# CH32M030C8T7-R0.net
KiCad netlist of a schematic drawn in Altium Designer
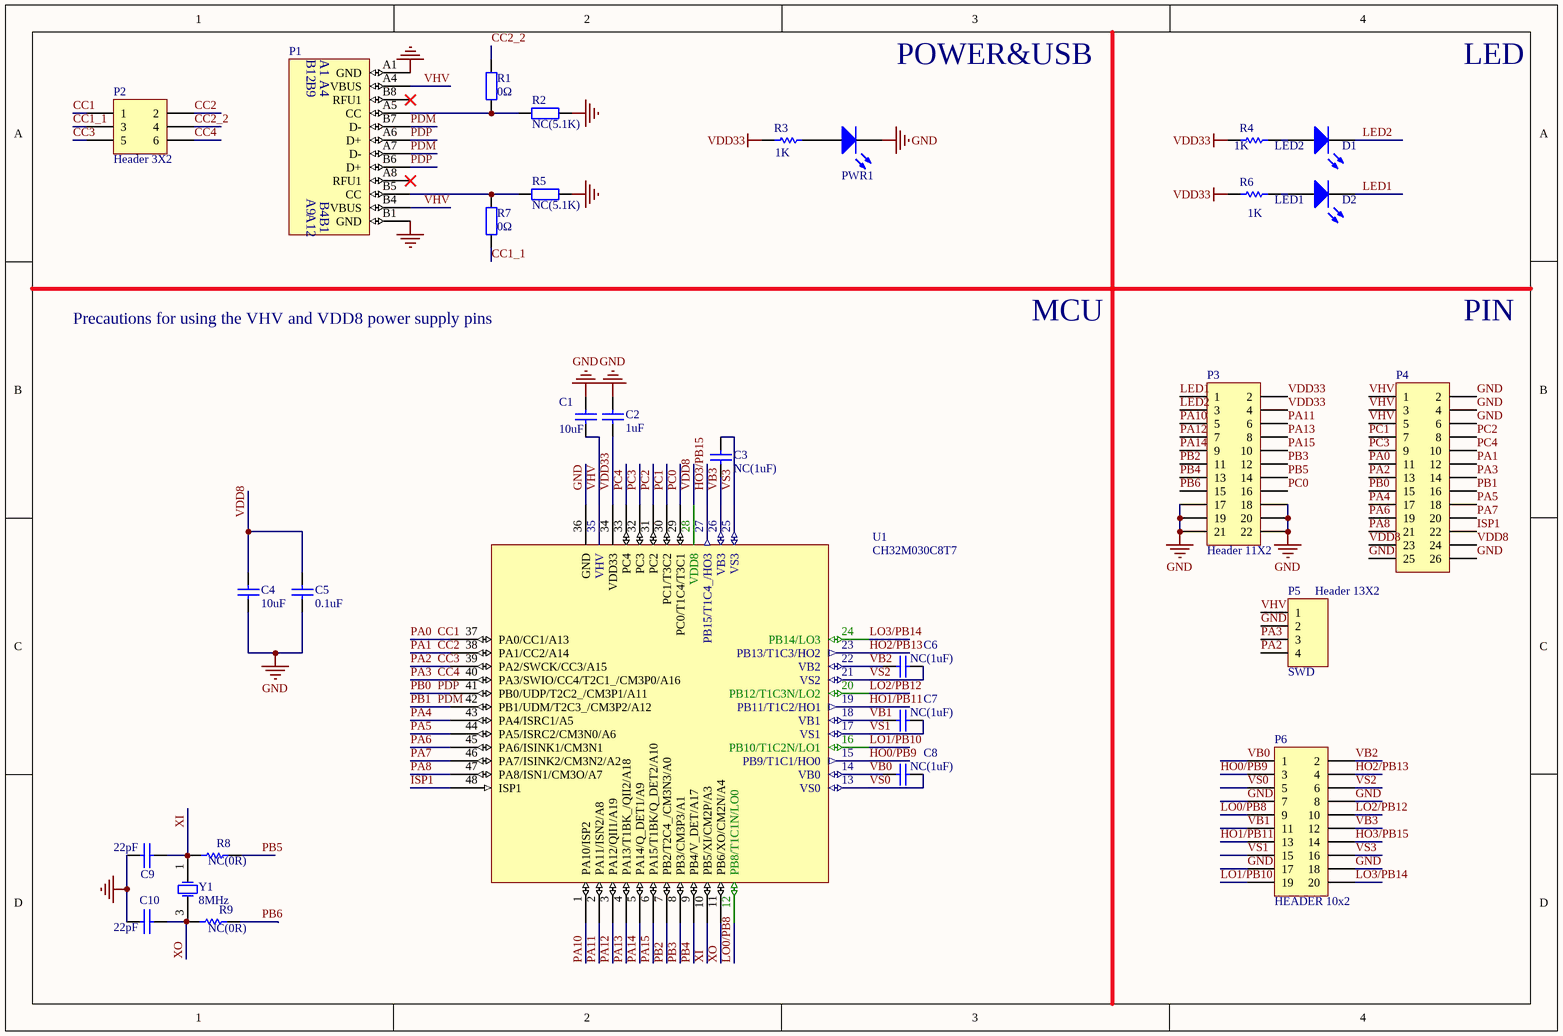
[diagram p0: CH32M030C8T7-R0.SchDoc]

(export (version "E")
  (design (tool "Eeschema 10.0.6"))
  (components
    (comp (ref "C1")
      (value "10uF")
      (footprint "0603_C")
      (description "Capacitor")
      (fields (field (name "PUBLISHER") "Altium Limited"))
      (libsource (lib "*") (part "Cap"))
    )
    (comp (ref "C2")
      (value "1uF")
      (footprint "0603_C")
      (description "Capacitor")
      (fields (field (name "PUBLISHER") "Altium Limited"))
      (libsource (lib "*") (part "Cap"))
    )
    (comp (ref "C3")
      (value "NC(1uF)")
      (footprint "0603_C")
      (description "Capacitor")
      (fields (field (name "PUBLISHER") "Altium Limited"))
      (libsource (lib "*") (part "Cap"))
    )
    (comp (ref "C4")
      (value "10uF")
      (footprint "0603_C")
      (description "Capacitor")
      (fields (field (name "PUBLISHER") "Altium Limited"))
      (libsource (lib "*") (part "Cap"))
    )
    (comp (ref "C5")
      (value "0.1uF")
      (footprint "0603_C")
      (description "Capacitor")
      (fields (field (name "PUBLISHER") "Altium Limited"))
      (libsource (lib "*") (part "Cap"))
    )
    (comp (ref "C6")
      (value "NC(1uF)")
      (footprint "0603_C")
      (description "Capacitor")
      (fields (field (name "PUBLISHER") "Altium Limited"))
      (libsource (lib "*") (part "Cap"))
    )
    (comp (ref "C7")
      (value "NC(1uF)")
      (footprint "0603_C")
      (description "Capacitor")
      (fields (field (name "PUBLISHER") "Altium Limited"))
      (libsource (lib "*") (part "Cap"))
    )
    (comp (ref "C8")
      (value "NC(1uF)")
      (footprint "0603_C")
      (description "Capacitor")
      (fields (field (name "PUBLISHER") "Altium Limited"))
      (libsource (lib "*") (part "Cap"))
    )
    (comp (ref "C9")
      (value "22pF")
      (footprint "0603_C")
      (description "Capacitor")
      (libsource (lib "*") (part "CAP"))
    )
    (comp (ref "C10")
      (value "22pF")
      (footprint "0603_C")
      (description "Capacitor")
      (libsource (lib "*") (part "CAP"))
    )
    (comp (ref "D1")
      (value "LED2")
      (footprint "0603+")
      (description "Typical INFRARED GaAs LED")
      (fields (field (name "PUBLISHER") "Altium Limited"))
      (libsource (lib "*") (part "LED0"))
    )
    (comp (ref "D2")
      (value "LED1")
      (footprint "0603+")
      (description "Typical INFRARED GaAs LED")
      (fields (field (name "PUBLISHER") "Altium Limited"))
      (libsource (lib "*") (part "LED0"))
    )
    (comp (ref "P1")
      (value "TYPE-C")
      (footprint "TYPE-C-Receptacle-2.0")
      (libsource (lib "*") (part "TYPE-C1"))
    )
    (comp (ref "P2")
      (value "Header 3X2")
      (footprint "IDC6-2.54mm")
      (description "Header, 3-Pin, Dual row")
      (fields (field (name "PUBLISHER") "Altium Limited"))
      (libsource (lib "Miscellaneous Connectors") (part "Header 3X2"))
    )
    (comp (ref "P3")
      (value "Header 11X2")
      (footprint "IDC22-2.54mm")
      (description "Header, 11-Pin, Dual row")
      (fields (field (name "PUBLISHER") "Altium Limited"))
      (libsource (lib "Miscellaneous Connectors") (part "Header 11X2"))
    )
    (comp (ref "P4")
      (value "Header 13X2")
      (footprint "IDC26-2.54mm")
      (description "Header, 13-Pin, Dual row")
      (fields (field (name "PUBLISHER") "Altium Limited"))
      (libsource (lib "Miscellaneous Connectors") (part "Header 13X2"))
    )
    (comp (ref "P5")
      (value "SWD")
      (footprint "SIP4-2.54mm")
      (description "Header, 4-Pin")
      (libsource (lib "wch_sch_others") (part "HEADER 4"))
    )
    (comp (ref "P6")
      (value "HEADER 10x2")
      (footprint "MYPCB:IDC20-2.54MM")
      (description "Header, 10-Pin, Dual row")
      (libsource (lib "wch_sch_others") (part "HEADER 10x2"))
    )
    (comp (ref "PWR1")
      (value "POWER  red")
      (footprint "0603+")
      (description "Typical INFRARED GaAs LED")
      (fields (field (name "PUBLISHER") "Altium Limited"))
      (libsource (lib "*") (part "LED0"))
    )
    (comp (ref "R1")
      (value "0Ω")
      (footprint "0603")
      (description "Resistor")
      (libsource (lib "") (part "Res2_1"))
    )
    (comp (ref "R2")
      (value "NC(5.1K)")
      (footprint "0603")
      (description "Resistor")
      (libsource (lib "Miscellaneous Devices") (part "Res2"))
    )
    (comp (ref "R3")
      (value "1K")
      (footprint "0603")
      (description "Semiconductor Resistor")
      (fields (field (name "PUBLISHER") "Altium Limited"))
      (libsource (lib "*") (part "Res Semi"))
    )
    (comp (ref "R4")
      (value "1K")
      (footprint "0603")
      (description "Semiconductor Resistor")
      (fields (field (name "PUBLISHER") "Altium Limited"))
      (libsource (lib "*") (part "Res Semi"))
    )
    (comp (ref "R5")
      (value "NC(5.1K)")
      (footprint "0603")
      (description "Resistor")
      (libsource (lib "Miscellaneous Devices") (part "Res2"))
    )
    (comp (ref "R6")
      (value "1K")
      (footprint "0603")
      (description "Semiconductor Resistor")
      (fields (field (name "PUBLISHER") "Altium Limited"))
      (libsource (lib "*") (part "Res Semi"))
    )
    (comp (ref "R7")
      (value "0Ω")
      (footprint "0603")
      (description "Resistor")
      (libsource (lib "") (part "Res2_1"))
    )
    (comp (ref "R8")
      (value "NC(0R)")
      (footprint "0603")
      (description "Semiconductor Resistor")
      (fields (field (name "PUBLISHER") "Altium Limited"))
      (libsource (lib "*") (part "Res Semi"))
    )
    (comp (ref "R9")
      (value "NC(0R)")
      (footprint "0603")
      (description "Semiconductor Resistor")
      (fields (field (name "PUBLISHER") "Altium Limited"))
      (libsource (lib "*") (part "Res Semi"))
    )
    (comp (ref "U1")
      (value "CH32M030C8T7")
      (footprint "LQFP48")
      (description "RISC-V MCU, 72MHz, USB, Type-C/PD, OPA, CMP, 28V gate driver")
      (libsource (lib "CHXXX") (part "CH32M030C8T7"))
    )
    (comp (ref "Y1")
      (value "8MHz")
      (footprint "XT3225")
      (description "Crystal Oscillator")
      (fields (field (name "PUBLISHER") "Altium Limited"))
      (libsource (lib "*") (part "XTAL"))
    )
  )
  (nets
    (net (code "1") (name "/CC1") (class "Default")
      (node (ref "P2") (pin "1") (pinfunction "1_1") (pintype "passive"))
      (node (ref "P4") (pin "11") (pinfunction "11_11") (pintype "passive"))
      (node (ref "U1") (pin "37") (pinfunction "PA0/CC1/A13_37") (pintype "bidirectional"))
    )
    (net (code "2") (name "/CC1_1") (class "Default")
      (node (ref "P2") (pin "3") (pinfunction "3_3") (pintype "passive"))
      (node (ref "R7") (pin "1") (pinfunction "1_1") (pintype "passive"))
    )
    (net (code "3") (name "/CC2") (class "Default")
      (node (ref "P2") (pin "2") (pinfunction "2_2") (pintype "passive"))
      (node (ref "P4") (pin "12") (pinfunction "12_12") (pintype "passive"))
      (node (ref "U1") (pin "38") (pinfunction "PA1/CC2/A14_38") (pintype "bidirectional"))
    )
    (net (code "4") (name "/CC2_2") (class "Default")
      (node (ref "P2") (pin "4") (pinfunction "4_4") (pintype "passive"))
      (node (ref "R1") (pin "2") (pinfunction "2_2") (pintype "passive"))
    )
    (net (code "5") (name "/CC3") (class "Default")
      (node (ref "P2") (pin "5") (pinfunction "5_5") (pintype "passive"))
      (node (ref "P4") (pin "13") (pinfunction "13_13") (pintype "passive"))
      (node (ref "P5") (pin "4") (pinfunction "4_4") (pintype "passive"))
      (node (ref "U1") (pin "39") (pinfunction "PA2/SWCK/CC3/A15_39") (pintype "bidirectional"))
    )
    (net (code "6") (name "/CC4") (class "Default")
      (node (ref "P2") (pin "6") (pinfunction "6_6") (pintype "passive"))
      (node (ref "P4") (pin "14") (pinfunction "14_14") (pintype "passive"))
      (node (ref "P5") (pin "3") (pinfunction "3_3") (pintype "passive"))
      (node (ref "U1") (pin "40") (pinfunction "PA3/SWIO/CC4/T2C1_/CM3P0/A16_40") (pintype "bidirectional"))
    )
    (net (code "7") (name "/HO0{slash}PB9") (class "Default")
      (node (ref "P6") (pin "3") (pinfunction "3_3") (pintype "passive"))
      (node (ref "U1") (pin "15") (pinfunction "PB9/T1C1/HO0_15") (pintype "output"))
    )
    (net (code "8") (name "/HO1{slash}PB11") (class "Default")
      (node (ref "P6") (pin "13") (pinfunction "13_13") (pintype "passive"))
      (node (ref "U1") (pin "19") (pinfunction "PB11/T1C2/HO1_19") (pintype "output"))
    )
    (net (code "9") (name "/HO2{slash}PB13") (class "Default")
      (node (ref "P6") (pin "4") (pinfunction "4_4") (pintype "passive"))
      (node (ref "U1") (pin "23") (pinfunction "PB13/T1C3/HO2_23") (pintype "output"))
    )
    (net (code "10") (name "/HO3{slash}PB15") (class "Default")
      (node (ref "P6") (pin "14") (pinfunction "14_14") (pintype "passive"))
      (node (ref "U1") (pin "27") (pinfunction "PB15/T1C4_/HO3_27") (pintype "output"))
    )
    (net (code "11") (name "/ISP1") (class "Default")
      (node (ref "P4") (pin "22") (pinfunction "22_22") (pintype "passive"))
      (node (ref "U1") (pin "48") (pinfunction "ISP1_48") (pintype "input"))
    )
    (net (code "12") (name "/LED1") (class "Default")
      (node (ref "D2") (pin "2") (pinfunction "K_2") (pintype "passive"))
      (node (ref "P3") (pin "1") (pinfunction "1_1") (pintype "passive"))
    )
    (net (code "13") (name "/LED2") (class "Default")
      (node (ref "D1") (pin "2") (pinfunction "K_2") (pintype "passive"))
      (node (ref "P3") (pin "3") (pinfunction "3_3") (pintype "passive"))
    )
    (net (code "14") (name "/LO0{slash}PB8") (class "Default")
      (node (ref "P6") (pin "9") (pinfunction "9_9") (pintype "passive"))
      (node (ref "U1") (pin "12") (pinfunction "PB8/T1C1N/LO0_12") (pintype "bidirectional"))
    )
    (net (code "15") (name "/LO1{slash}PB10") (class "Default")
      (node (ref "P6") (pin "19") (pinfunction "19_19") (pintype "passive"))
      (node (ref "U1") (pin "16") (pinfunction "PB10/T1C2N/LO1_16") (pintype "bidirectional"))
    )
    (net (code "16") (name "/LO2{slash}PB12") (class "Default")
      (node (ref "P6") (pin "10") (pinfunction "10_10") (pintype "passive"))
      (node (ref "U1") (pin "20") (pinfunction "PB12/T1C3N/LO2_20") (pintype "bidirectional"))
    )
    (net (code "17") (name "/LO3{slash}PB14") (class "Default")
      (node (ref "P6") (pin "20") (pinfunction "20_20") (pintype "passive"))
      (node (ref "U1") (pin "24") (pinfunction "PB14/LO3_24") (pintype "bidirectional"))
    )
    (net (code "18") (name "/PA4") (class "Default")
      (node (ref "P4") (pin "17") (pinfunction "17_17") (pintype "passive"))
      (node (ref "U1") (pin "43") (pinfunction "PA4/ISRC1/A5_43") (pintype "bidirectional"))
    )
    (net (code "19") (name "/PA5") (class "Default")
      (node (ref "P4") (pin "18") (pinfunction "18_18") (pintype "passive"))
      (node (ref "U1") (pin "44") (pinfunction "PA5/ISRC2/CM3N0/A6_44") (pintype "bidirectional"))
    )
    (net (code "20") (name "/PA6") (class "Default")
      (node (ref "P4") (pin "19") (pinfunction "19_19") (pintype "passive"))
      (node (ref "U1") (pin "45") (pinfunction "PA6/ISINK1/CM3N1_45") (pintype "bidirectional"))
    )
    (net (code "21") (name "/PA7") (class "Default")
      (node (ref "P4") (pin "20") (pinfunction "20_20") (pintype "passive"))
      (node (ref "U1") (pin "46") (pinfunction "PA7/ISINK2/CM3N2/A2_46") (pintype "bidirectional"))
    )
    (net (code "22") (name "/PA8") (class "Default")
      (node (ref "P4") (pin "21") (pinfunction "21_21") (pintype "passive"))
      (node (ref "U1") (pin "47") (pinfunction "PA8/ISN1/CM3O/A7_47") (pintype "bidirectional"))
    )
    (net (code "23") (name "/PA10") (class "Default")
      (node (ref "P3") (pin "5") (pinfunction "5_5") (pintype "passive"))
      (node (ref "U1") (pin "1") (pinfunction "PA10/ISP2_1") (pintype "bidirectional"))
    )
    (net (code "24") (name "/PA11") (class "Default")
      (node (ref "P3") (pin "6") (pinfunction "6_6") (pintype "passive"))
      (node (ref "U1") (pin "2") (pinfunction "PA11/ISN2/A8_2") (pintype "bidirectional"))
    )
    (net (code "25") (name "/PA12") (class "Default")
      (node (ref "P3") (pin "7") (pinfunction "7_7") (pintype "passive"))
      (node (ref "U1") (pin "3") (pinfunction "PA12/QII1/A19_3") (pintype "bidirectional"))
    )
    (net (code "26") (name "/PA13") (class "Default")
      (node (ref "P3") (pin "8") (pinfunction "8_8") (pintype "passive"))
      (node (ref "U1") (pin "4") (pinfunction "PA13/T1BK_/QII2/A18_4") (pintype "bidirectional"))
    )
    (net (code "27") (name "/PA14") (class "Default")
      (node (ref "P3") (pin "9") (pinfunction "9_9") (pintype "passive"))
      (node (ref "U1") (pin "5") (pinfunction "PA14/Q_DET1/A9_5") (pintype "bidirectional"))
    )
    (net (code "28") (name "/PA15") (class "Default")
      (node (ref "P3") (pin "10") (pinfunction "10_10") (pintype "passive"))
      (node (ref "U1") (pin "6") (pinfunction "PA15/T1BK/Q_DET2/A10_6") (pintype "bidirectional"))
    )
    (net (code "29") (name "/PB0") (class "Default")
      (node (ref "P1") (pin "A6") (pinfunction "D+_A6") (pintype "bidirectional"))
      (node (ref "P1") (pin "B6") (pinfunction "D+_B6") (pintype "bidirectional"))
      (node (ref "P4") (pin "15") (pinfunction "15_15") (pintype "passive"))
      (node (ref "U1") (pin "41") (pinfunction "PB0/UDP/T2C2_/CM3P1/A11_41") (pintype "bidirectional"))
    )
    (net (code "30") (name "/PB1") (class "Default")
      (node (ref "P1") (pin "A7") (pinfunction "D-_A7") (pintype "bidirectional"))
      (node (ref "P1") (pin "B7") (pinfunction "D-_B7") (pintype "bidirectional"))
      (node (ref "P4") (pin "16") (pinfunction "16_16") (pintype "passive"))
      (node (ref "U1") (pin "42") (pinfunction "PB1/UDM/T2C3_/CM3P2/A12_42") (pintype "bidirectional"))
    )
    (net (code "31") (name "/PB2") (class "Default")
      (node (ref "P3") (pin "11") (pinfunction "11_11") (pintype "passive"))
      (node (ref "U1") (pin "7") (pinfunction "PB2/T2C4_/CM3N3/A0_7") (pintype "bidirectional"))
    )
    (net (code "32") (name "/PB3") (class "Default")
      (node (ref "P3") (pin "12") (pinfunction "12_12") (pintype "passive"))
      (node (ref "U1") (pin "8") (pinfunction "PB3/CM3P3/A1_8") (pintype "bidirectional"))
    )
    (net (code "33") (name "/PB4") (class "Default")
      (node (ref "P3") (pin "13") (pinfunction "13_13") (pintype "passive"))
      (node (ref "U1") (pin "9") (pinfunction "PB4/V_DET/A17_9") (pintype "bidirectional"))
    )
    (net (code "34") (name "/PB5") (class "Default")
      (node (ref "P3") (pin "14") (pinfunction "14_14") (pintype "passive"))
      (node (ref "R8") (pin "2") (pinfunction "2_2") (pintype "passive"))
    )
    (net (code "35") (name "/PB6") (class "Default")
      (node (ref "P3") (pin "15") (pinfunction "15_15") (pintype "passive"))
      (node (ref "R9") (pin "2") (pinfunction "2_2") (pintype "passive"))
    )
    (net (code "36") (name "/PC0") (class "Default")
      (node (ref "P3") (pin "16") (pinfunction "16_16") (pintype "passive"))
      (node (ref "U1") (pin "29") (pinfunction "PC0/T1C4/T3C1_29") (pintype "bidirectional"))
    )
    (net (code "37") (name "/PC1") (class "Default")
      (node (ref "P4") (pin "7") (pinfunction "7_7") (pintype "passive"))
      (node (ref "U1") (pin "30") (pinfunction "PC1/T3C2_30") (pintype "bidirectional"))
    )
    (net (code "38") (name "/PC2") (class "Default")
      (node (ref "P4") (pin "8") (pinfunction "8_8") (pintype "passive"))
      (node (ref "U1") (pin "31") (pinfunction "PC2_31") (pintype "bidirectional"))
    )
    (net (code "39") (name "/PC3") (class "Default")
      (node (ref "P4") (pin "9") (pinfunction "9_9") (pintype "passive"))
      (node (ref "U1") (pin "32") (pinfunction "PC3_32") (pintype "bidirectional"))
    )
    (net (code "40") (name "/PC4") (class "Default")
      (node (ref "P4") (pin "10") (pinfunction "10_10") (pintype "passive"))
      (node (ref "U1") (pin "33") (pinfunction "PC4_33") (pintype "bidirectional"))
    )
    (net (code "41") (name "/VB0") (class "Default")
      (node (ref "C8") (pin "2") (pinfunction "2_2") (pintype "passive"))
      (node (ref "P6") (pin "1") (pinfunction "1_1") (pintype "passive"))
      (node (ref "U1") (pin "14") (pinfunction "VB0_14") (pintype "bidirectional"))
    )
    (net (code "42") (name "/VB1") (class "Default")
      (node (ref "C7") (pin "2") (pinfunction "2_2") (pintype "passive"))
      (node (ref "P6") (pin "11") (pinfunction "11_11") (pintype "passive"))
      (node (ref "U1") (pin "18") (pinfunction "VB1_18") (pintype "bidirectional"))
    )
    (net (code "43") (name "/VB2") (class "Default")
      (node (ref "C6") (pin "2") (pinfunction "2_2") (pintype "passive"))
      (node (ref "P6") (pin "2") (pinfunction "2_2") (pintype "passive"))
      (node (ref "U1") (pin "22") (pinfunction "VB2_22") (pintype "bidirectional"))
    )
    (net (code "44") (name "/VB3") (class "Default")
      (node (ref "C3") (pin "2") (pinfunction "2_2") (pintype "passive"))
      (node (ref "P6") (pin "12") (pinfunction "12_12") (pintype "passive"))
      (node (ref "U1") (pin "26") (pinfunction "VB3_26") (pintype "bidirectional"))
    )
    (net (code "45") (name "/VDD8") (class "Default")
      (node (ref "C4") (pin "2") (pinfunction "2_2") (pintype "passive"))
      (node (ref "C5") (pin "2") (pinfunction "2_2") (pintype "passive"))
      (node (ref "P4") (pin "23") (pinfunction "23_23") (pintype "passive"))
      (node (ref "P4") (pin "24") (pinfunction "24_24") (pintype "passive"))
      (node (ref "U1") (pin "28") (pinfunction "VDD8_28") (pintype "power_in"))
    )
    (net (code "46") (name "/VHV") (class "Default")
      (node (ref "C1") (pin "1") (pinfunction "1_1") (pintype "passive"))
      (node (ref "P1") (pin "A4") (pinfunction "VBUS_A4") (pintype "bidirectional"))
      (node (ref "P1") (pin "B4") (pinfunction "VBUS_B4") (pintype "bidirectional"))
      (node (ref "P4") (pin "1") (pinfunction "1_1") (pintype "passive"))
      (node (ref "P4") (pin "3") (pinfunction "3_3") (pintype "passive"))
      (node (ref "P4") (pin "5") (pinfunction "5_5") (pintype "passive"))
      (node (ref "P5") (pin "1") (pinfunction "1_1") (pintype "passive"))
      (node (ref "U1") (pin "35") (pinfunction "VHV_35") (pintype "power_in"))
    )
    (net (code "47") (name "/VS0") (class "Default")
      (node (ref "C8") (pin "1") (pinfunction "1_1") (pintype "passive"))
      (node (ref "P6") (pin "5") (pinfunction "5_5") (pintype "passive"))
      (node (ref "U1") (pin "13") (pinfunction "VS0_13") (pintype "bidirectional"))
    )
    (net (code "48") (name "/VS1") (class "Default")
      (node (ref "C7") (pin "1") (pinfunction "1_1") (pintype "passive"))
      (node (ref "P6") (pin "15") (pinfunction "15_15") (pintype "passive"))
      (node (ref "U1") (pin "17") (pinfunction "VS1_17") (pintype "bidirectional"))
    )
    (net (code "49") (name "/VS2") (class "Default")
      (node (ref "C6") (pin "1") (pinfunction "1_1") (pintype "passive"))
      (node (ref "P6") (pin "6") (pinfunction "6_6") (pintype "passive"))
      (node (ref "U1") (pin "21") (pinfunction "VS2_21") (pintype "bidirectional"))
    )
    (net (code "50") (name "/VS3") (class "Default")
      (node (ref "C3") (pin "1") (pinfunction "1_1") (pintype "passive"))
      (node (ref "P6") (pin "16") (pinfunction "16_16") (pintype "passive"))
      (node (ref "U1") (pin "25") (pinfunction "VS3_25") (pintype "bidirectional"))
    )
    (net (code "51") (name "/XI") (class "Default")
      (node (ref "C9") (pin "2") (pinfunction "2_2") (pintype "passive"))
      (node (ref "R8") (pin "1") (pinfunction "1_1") (pintype "passive"))
      (node (ref "U1") (pin "10") (pinfunction "PB5/XI/CM2P/A3_10") (pintype "bidirectional"))
      (node (ref "Y1") (pin "1") (pinfunction "OSC1_1") (pintype "passive"))
    )
    (net (code "52") (name "/XO") (class "Default")
      (node (ref "C10") (pin "2") (pinfunction "2_2") (pintype "passive"))
      (node (ref "R9") (pin "1") (pinfunction "1_1") (pintype "passive"))
      (node (ref "U1") (pin "11") (pinfunction "PB6/XO/CM2N/A4_11") (pintype "bidirectional"))
    )
    (net (code "53") (name "GND") (class "Default")
      (node (ref "C1") (pin "2") (pinfunction "2_2") (pintype "passive"))
      (node (ref "C10") (pin "1") (pinfunction "1_1") (pintype "passive"))
      (node (ref "C2") (pin "2") (pinfunction "2_2") (pintype "passive"))
      (node (ref "C4") (pin "1") (pinfunction "1_1") (pintype "passive"))
      (node (ref "C5") (pin "1") (pinfunction "1_1") (pintype "passive"))
      (node (ref "C9") (pin "1") (pinfunction "1_1") (pintype "passive"))
      (node (ref "P1") (pin "A1") (pinfunction "GND_A1") (pintype "bidirectional"))
      (node (ref "P1") (pin "B1") (pinfunction "GND_B1") (pintype "bidirectional"))
      (node (ref "P3") (pin "17") (pinfunction "17_17") (pintype "passive"))
      (node (ref "P3") (pin "18") (pinfunction "18_18") (pintype "passive"))
      (node (ref "P3") (pin "19") (pinfunction "19_19") (pintype "passive"))
      (node (ref "P3") (pin "20") (pinfunction "20_20") (pintype "passive"))
      (node (ref "P3") (pin "21") (pinfunction "21_21") (pintype "passive"))
      (node (ref "P3") (pin "22") (pinfunction "22_22") (pintype "passive"))
      (node (ref "P4") (pin "2") (pinfunction "2_2") (pintype "passive"))
      (node (ref "P4") (pin "25") (pinfunction "25_25") (pintype "passive"))
      (node (ref "P4") (pin "26") (pinfunction "26_26") (pintype "passive"))
      (node (ref "P4") (pin "4") (pinfunction "4_4") (pintype "passive"))
      (node (ref "P4") (pin "6") (pinfunction "6_6") (pintype "passive"))
      (node (ref "P5") (pin "2") (pinfunction "2_2") (pintype "passive"))
      (node (ref "P6") (pin "17") (pinfunction "17_17") (pintype "passive"))
      (node (ref "P6") (pin "18") (pinfunction "18_18") (pintype "passive"))
      (node (ref "P6") (pin "7") (pinfunction "7_7") (pintype "passive"))
      (node (ref "P6") (pin "8") (pinfunction "8_8") (pintype "passive"))
      (node (ref "PWR1") (pin "2") (pinfunction "K_2") (pintype "passive"))
      (node (ref "R2") (pin "2") (pinfunction "2_2") (pintype "passive"))
      (node (ref "R5") (pin "2") (pinfunction "2_2") (pintype "passive"))
      (node (ref "U1") (pin "36") (pinfunction "GND_36") (pintype "power_in"))
    )
    (net (code "54") (name "Net-(D1-A)") (class "Default")
      (node (ref "D1") (pin "1") (pinfunction "A_1") (pintype "passive"))
      (node (ref "R4") (pin "2") (pinfunction "2_2") (pintype "passive"))
    )
    (net (code "55") (name "Net-(D2-A)") (class "Default")
      (node (ref "D2") (pin "1") (pinfunction "A_1") (pintype "passive"))
      (node (ref "R6") (pin "2") (pinfunction "2_2") (pintype "passive"))
    )
    (net (code "56") (name "Net-(P1-CC-PadA5)") (class "Default")
      (node (ref "P1") (pin "A5") (pinfunction "CC_A5") (pintype "bidirectional"))
      (node (ref "R1") (pin "1") (pinfunction "1_1") (pintype "passive"))
      (node (ref "R2") (pin "1") (pinfunction "1_1") (pintype "passive"))
    )
    (net (code "57") (name "Net-(P1-CC-PadB5)") (class "Default")
      (node (ref "P1") (pin "B5") (pinfunction "CC_B5") (pintype "bidirectional"))
      (node (ref "R5") (pin "1") (pinfunction "1_1") (pintype "passive"))
      (node (ref "R7") (pin "2") (pinfunction "2_2") (pintype "passive"))
    )
    (net (code "58") (name "Net-(PWR1-A)") (class "Default")
      (node (ref "PWR1") (pin "1") (pinfunction "A_1") (pintype "passive"))
      (node (ref "R3") (pin "1") (pinfunction "1_1") (pintype "passive"))
    )
    (net (code "59") (name "VDD33") (class "Default")
      (node (ref "C2") (pin "1") (pinfunction "1_1") (pintype "passive"))
      (node (ref "P3") (pin "2") (pinfunction "2_2") (pintype "passive"))
      (node (ref "P3") (pin "4") (pinfunction "4_4") (pintype "passive"))
      (node (ref "R3") (pin "2") (pinfunction "2_2") (pintype "passive"))
      (node (ref "R4") (pin "1") (pinfunction "1_1") (pintype "passive"))
      (node (ref "R6") (pin "1") (pinfunction "1_1") (pintype "passive"))
      (node (ref "U1") (pin "34") (pinfunction "VDD33_34") (pintype "power_in"))
    )
    (net (code "60") (name "unconnected-(P1-RFU1-PadA8)") (class "Default")
      (node (ref "P1") (pin "A8") (pinfunction "RFU1_A8") (pintype "bidirectional+no_connect"))
    )
    (net (code "61") (name "unconnected-(P1-RFU1-PadB8)") (class "Default")
      (node (ref "P1") (pin "B8") (pinfunction "RFU1_B8") (pintype "bidirectional+no_connect"))
    )
    (net (code "62") (name "unconnected-(Y1-OSC2-Pad3)") (class "Default")
      (node (ref "Y1") (pin "3") (pinfunction "OSC2_3") (pintype "passive"))
    )
  )
)
